# fan_control.net
KiCad netlist of a schematic drawn in Altium Designer
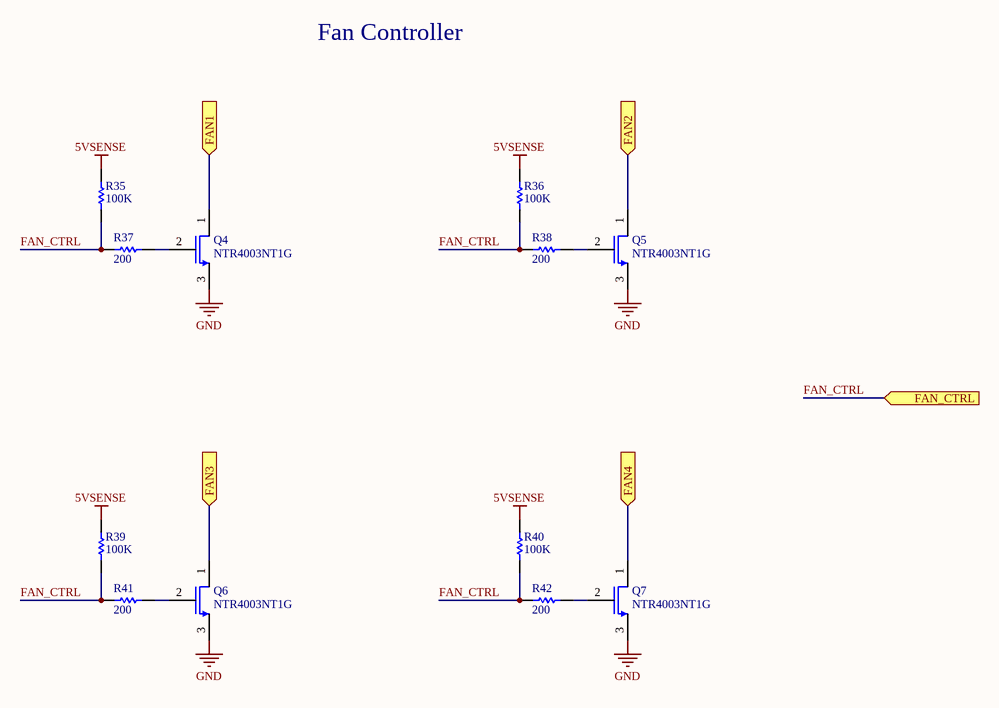
[diagram p0: fan_control.SchDoc]

(export (version "E")
  (design (tool "Eeschema 10.0.6"))
  (components
    (comp (ref "Q4")
      (value "NTR4003NT1G")
      (footprint "SOT-23")
      (description "MOSFET N-CH 30V 500MA SOT-23")
      (fields (field (name "MANUFACTURER") "ON Semiconductor"))
      (libsource (lib "common") (part "NTR4003NT1G"))
    )
    (comp (ref "Q5")
      (value "NTR4003NT1G")
      (footprint "SOT-23")
      (description "MOSFET N-CH 30V 500MA SOT-23")
      (fields (field (name "MANUFACTURER") "ON Semiconductor"))
      (libsource (lib "common") (part "NTR4003NT1G"))
    )
    (comp (ref "Q6")
      (value "NTR4003NT1G")
      (footprint "SOT-23")
      (description "MOSFET N-CH 30V 500MA SOT-23")
      (fields (field (name "MANUFACTURER") "ON Semiconductor"))
      (libsource (lib "common") (part "NTR4003NT1G"))
    )
    (comp (ref "Q7")
      (value "NTR4003NT1G")
      (footprint "SOT-23")
      (description "MOSFET N-CH 30V 500MA SOT-23")
      (fields (field (name "MANUFACTURER") "ON Semiconductor"))
      (libsource (lib "common") (part "NTR4003NT1G"))
    )
    (comp (ref "R35")
      (value "100K")
      (footprint "RESC1608N")
      (description "Resistor")
      (fields
        (field (name "MANUFACTURER") "Yageo")
        (field (name "MANUFACTURER PART NUMBER") "RC0603JR-07100KL")
        (field (name "PUBLISHER") "Altium Limited")
      )
      (libsource (lib "Miscellaneous Devices") (part "Res1"))
    )
    (comp (ref "R36")
      (value "100K")
      (footprint "RESC1608N")
      (description "Resistor")
      (fields
        (field (name "MANUFACTURER") "Yageo")
        (field (name "MANUFACTURER PART NUMBER") "RC0603JR-07100KL")
        (field (name "PUBLISHER") "Altium Limited")
      )
      (libsource (lib "Miscellaneous Devices") (part "Res1"))
    )
    (comp (ref "R37")
      (value "200")
      (footprint "RESC1608N")
      (description "Resistor")
      (fields
        (field (name "MANUFACTURER") "Yageo")
        (field (name "MANUFACTURER PART NUMBER") "RC0603JR-07200RL")
        (field (name "PUBLISHER") "Altium Limited")
      )
      (libsource (lib "Miscellaneous Devices") (part "Res1"))
    )
    (comp (ref "R38")
      (value "200")
      (footprint "RESC1608N")
      (description "Resistor")
      (fields
        (field (name "MANUFACTURER") "Yageo")
        (field (name "MANUFACTURER PART NUMBER") "RC0603JR-07200RL")
        (field (name "PUBLISHER") "Altium Limited")
      )
      (libsource (lib "Miscellaneous Devices") (part "Res1"))
    )
    (comp (ref "R39")
      (value "100K")
      (footprint "RESC1608N")
      (description "Resistor")
      (fields
        (field (name "MANUFACTURER") "Yageo")
        (field (name "MANUFACTURER PART NUMBER") "RC0603JR-07100KL")
        (field (name "PUBLISHER") "Altium Limited")
      )
      (libsource (lib "Miscellaneous Devices") (part "Res1"))
    )
    (comp (ref "R40")
      (value "100K")
      (footprint "RESC1608N")
      (description "Resistor")
      (fields
        (field (name "MANUFACTURER") "Yageo")
        (field (name "MANUFACTURER PART NUMBER") "RC0603JR-07100KL")
        (field (name "PUBLISHER") "Altium Limited")
      )
      (libsource (lib "Miscellaneous Devices") (part "Res1"))
    )
    (comp (ref "R41")
      (value "200")
      (footprint "RESC1608N")
      (description "Resistor")
      (fields
        (field (name "MANUFACTURER") "Yageo")
        (field (name "MANUFACTURER PART NUMBER") "RC0603JR-07200RL")
        (field (name "PUBLISHER") "Altium Limited")
      )
      (libsource (lib "Miscellaneous Devices") (part "Res1"))
    )
    (comp (ref "R42")
      (value "200")
      (footprint "RESC1608N")
      (description "Resistor")
      (fields
        (field (name "MANUFACTURER") "Yageo")
        (field (name "MANUFACTURER PART NUMBER") "RC0603JR-07200RL")
        (field (name "PUBLISHER") "Altium Limited")
      )
      (libsource (lib "Miscellaneous Devices") (part "Res1"))
    )
  )
  (nets
    (net (code "1") (name "/FAN1") (class "Default")
      (node (ref "Q4") (pin "1") (pinfunction "1_1") (pintype "passive"))
    )
    (net (code "2") (name "/FAN2") (class "Default")
      (node (ref "Q5") (pin "1") (pinfunction "1_1") (pintype "passive"))
    )
    (net (code "3") (name "/FAN3") (class "Default")
      (node (ref "Q6") (pin "1") (pinfunction "1_1") (pintype "passive"))
    )
    (net (code "4") (name "/FAN4") (class "Default")
      (node (ref "Q7") (pin "1") (pinfunction "1_1") (pintype "passive"))
    )
    (net (code "5") (name "/FAN_CTRL") (class "Default")
      (node (ref "R35") (pin "1") (pinfunction "1_1") (pintype "passive"))
      (node (ref "R36") (pin "1") (pinfunction "1_1") (pintype "passive"))
      (node (ref "R37") (pin "2") (pinfunction "2_2") (pintype "passive"))
      (node (ref "R38") (pin "2") (pinfunction "2_2") (pintype "passive"))
      (node (ref "R39") (pin "1") (pinfunction "1_1") (pintype "passive"))
      (node (ref "R40") (pin "1") (pinfunction "1_1") (pintype "passive"))
      (node (ref "R41") (pin "2") (pinfunction "2_2") (pintype "passive"))
      (node (ref "R42") (pin "2") (pinfunction "2_2") (pintype "passive"))
    )
    (net (code "6") (name "5VSENSE") (class "Default")
      (node (ref "R35") (pin "2") (pinfunction "2_2") (pintype "passive"))
      (node (ref "R36") (pin "2") (pinfunction "2_2") (pintype "passive"))
      (node (ref "R39") (pin "2") (pinfunction "2_2") (pintype "passive"))
      (node (ref "R40") (pin "2") (pinfunction "2_2") (pintype "passive"))
    )
    (net (code "7") (name "GND") (class "Default")
      (node (ref "Q4") (pin "3") (pinfunction "3_3") (pintype "passive"))
      (node (ref "Q5") (pin "3") (pinfunction "3_3") (pintype "passive"))
      (node (ref "Q6") (pin "3") (pinfunction "3_3") (pintype "passive"))
      (node (ref "Q7") (pin "3") (pinfunction "3_3") (pintype "passive"))
    )
    (net (code "8") (name "Net-(Q4-Pad2)") (class "Default")
      (node (ref "Q4") (pin "2") (pinfunction "2_2") (pintype "passive"))
      (node (ref "R37") (pin "1") (pinfunction "1_1") (pintype "passive"))
    )
    (net (code "9") (name "Net-(Q5-Pad2)") (class "Default")
      (node (ref "Q5") (pin "2") (pinfunction "2_2") (pintype "passive"))
      (node (ref "R38") (pin "1") (pinfunction "1_1") (pintype "passive"))
    )
    (net (code "10") (name "Net-(Q6-Pad2)") (class "Default")
      (node (ref "Q6") (pin "2") (pinfunction "2_2") (pintype "passive"))
      (node (ref "R41") (pin "1") (pinfunction "1_1") (pintype "passive"))
    )
    (net (code "11") (name "Net-(Q7-Pad2)") (class "Default")
      (node (ref "Q7") (pin "2") (pinfunction "2_2") (pintype "passive"))
      (node (ref "R42") (pin "1") (pinfunction "1_1") (pintype "passive"))
    )
  )
)
